# exercise2.net
KiCad netlist of a schematic drawn in Altium Designer
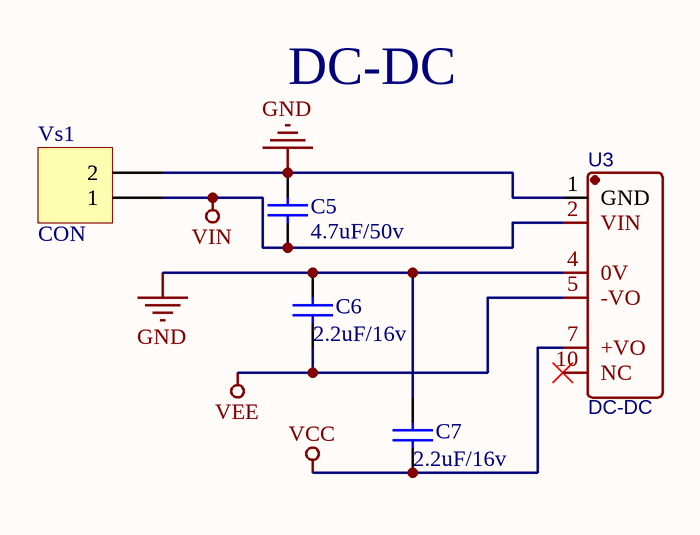
[diagram p0: exercise2.SchDoc]

(export (version "E")
  (design (tool "Eeschema 10.0.6"))
  (components
    (comp (ref "C5")
      (value "4.7uF/50v")
      (footprint "RAD-0.3")
      (description "Capacitor")
      (fields (field (name "Comment") "Cap") (field (name "PUBLISHER") "Altium Limited"))
      (libsource (lib "Miscellaneous Devices") (part "Cap"))
    )
    (comp (ref "C6")
      (value "2.2uF/16v")
      (footprint "RAD-0.3")
      (description "Capacitor")
      (fields (field (name "Comment") "Cap") (field (name "PUBLISHER") "Altium Limited"))
      (libsource (lib "Miscellaneous Devices") (part "Cap"))
    )
    (comp (ref "C7")
      (value "2.2uF/16v")
      (footprint "RAD-0.3")
      (description "Capacitor")
      (fields (field (name "Comment") "Cap") (field (name "PUBLISHER") "Altium Limited"))
      (libsource (lib "Miscellaneous Devices") (part "Cap"))
    )
    (comp (ref "U3")
      (value "DC-DC")
      (footprint "DC-DC")
      (fields
        (field (name "BOM_MANUFACTURER PART") "A0515XT-1WR2")
        (field (name "BOM_SUPPLIER PART") "C58972")
      )
      (libsource (lib "dzsx") (part "DC-DC"))
    )
    (comp (ref "Vs1")
      (value "CON")
      (footprint "HDR1X2")
      (description "Header, 2-Pin")
      (fields (field (name "PUBLISHER") "Altium Limited"))
      (libsource (lib "Miscellaneous Connectors") (part "Header 2"))
    )
  )
  (nets
    (net (code "1") (name "GND") (class "Default")
      (node (ref "C5") (pin "2") (pinfunction "2_2") (pintype "passive"))
      (node (ref "C6") (pin "2") (pinfunction "2_2") (pintype "passive"))
      (node (ref "C7") (pin "2") (pinfunction "2_2") (pintype "passive"))
      (node (ref "U3") (pin "1") (pinfunction "GND_1") (pintype "passive"))
      (node (ref "U3") (pin "4") (pinfunction "0V_4") (pintype "passive"))
      (node (ref "Vs1") (pin "2") (pinfunction "2_2") (pintype "passive"))
    )
    (net (code "2") (name "VCC") (class "Default")
      (node (ref "C7") (pin "1") (pinfunction "1_1") (pintype "passive"))
      (node (ref "U3") (pin "7") (pinfunction "+VO_7") (pintype "passive"))
    )
    (net (code "3") (name "VEE") (class "Default")
      (node (ref "C6") (pin "1") (pinfunction "1_1") (pintype "passive"))
      (node (ref "U3") (pin "5") (pinfunction "-VO_5") (pintype "passive"))
    )
    (net (code "4") (name "VIN") (class "Default")
      (node (ref "C5") (pin "1") (pinfunction "1_1") (pintype "passive"))
      (node (ref "U3") (pin "2") (pinfunction "VIN_2") (pintype "passive"))
      (node (ref "Vs1") (pin "1") (pinfunction "1_1") (pintype "passive"))
    )
    (net (code "5") (name "unconnected-(U3-NC-Pad10)") (class "Default")
      (node (ref "U3") (pin "10") (pinfunction "NC_10") (pintype "passive+no_connect"))
    )
  )
)
